# 1-Schematic_EE463_Project.net
KiCad netlist of a schematic drawn in EasyEDA
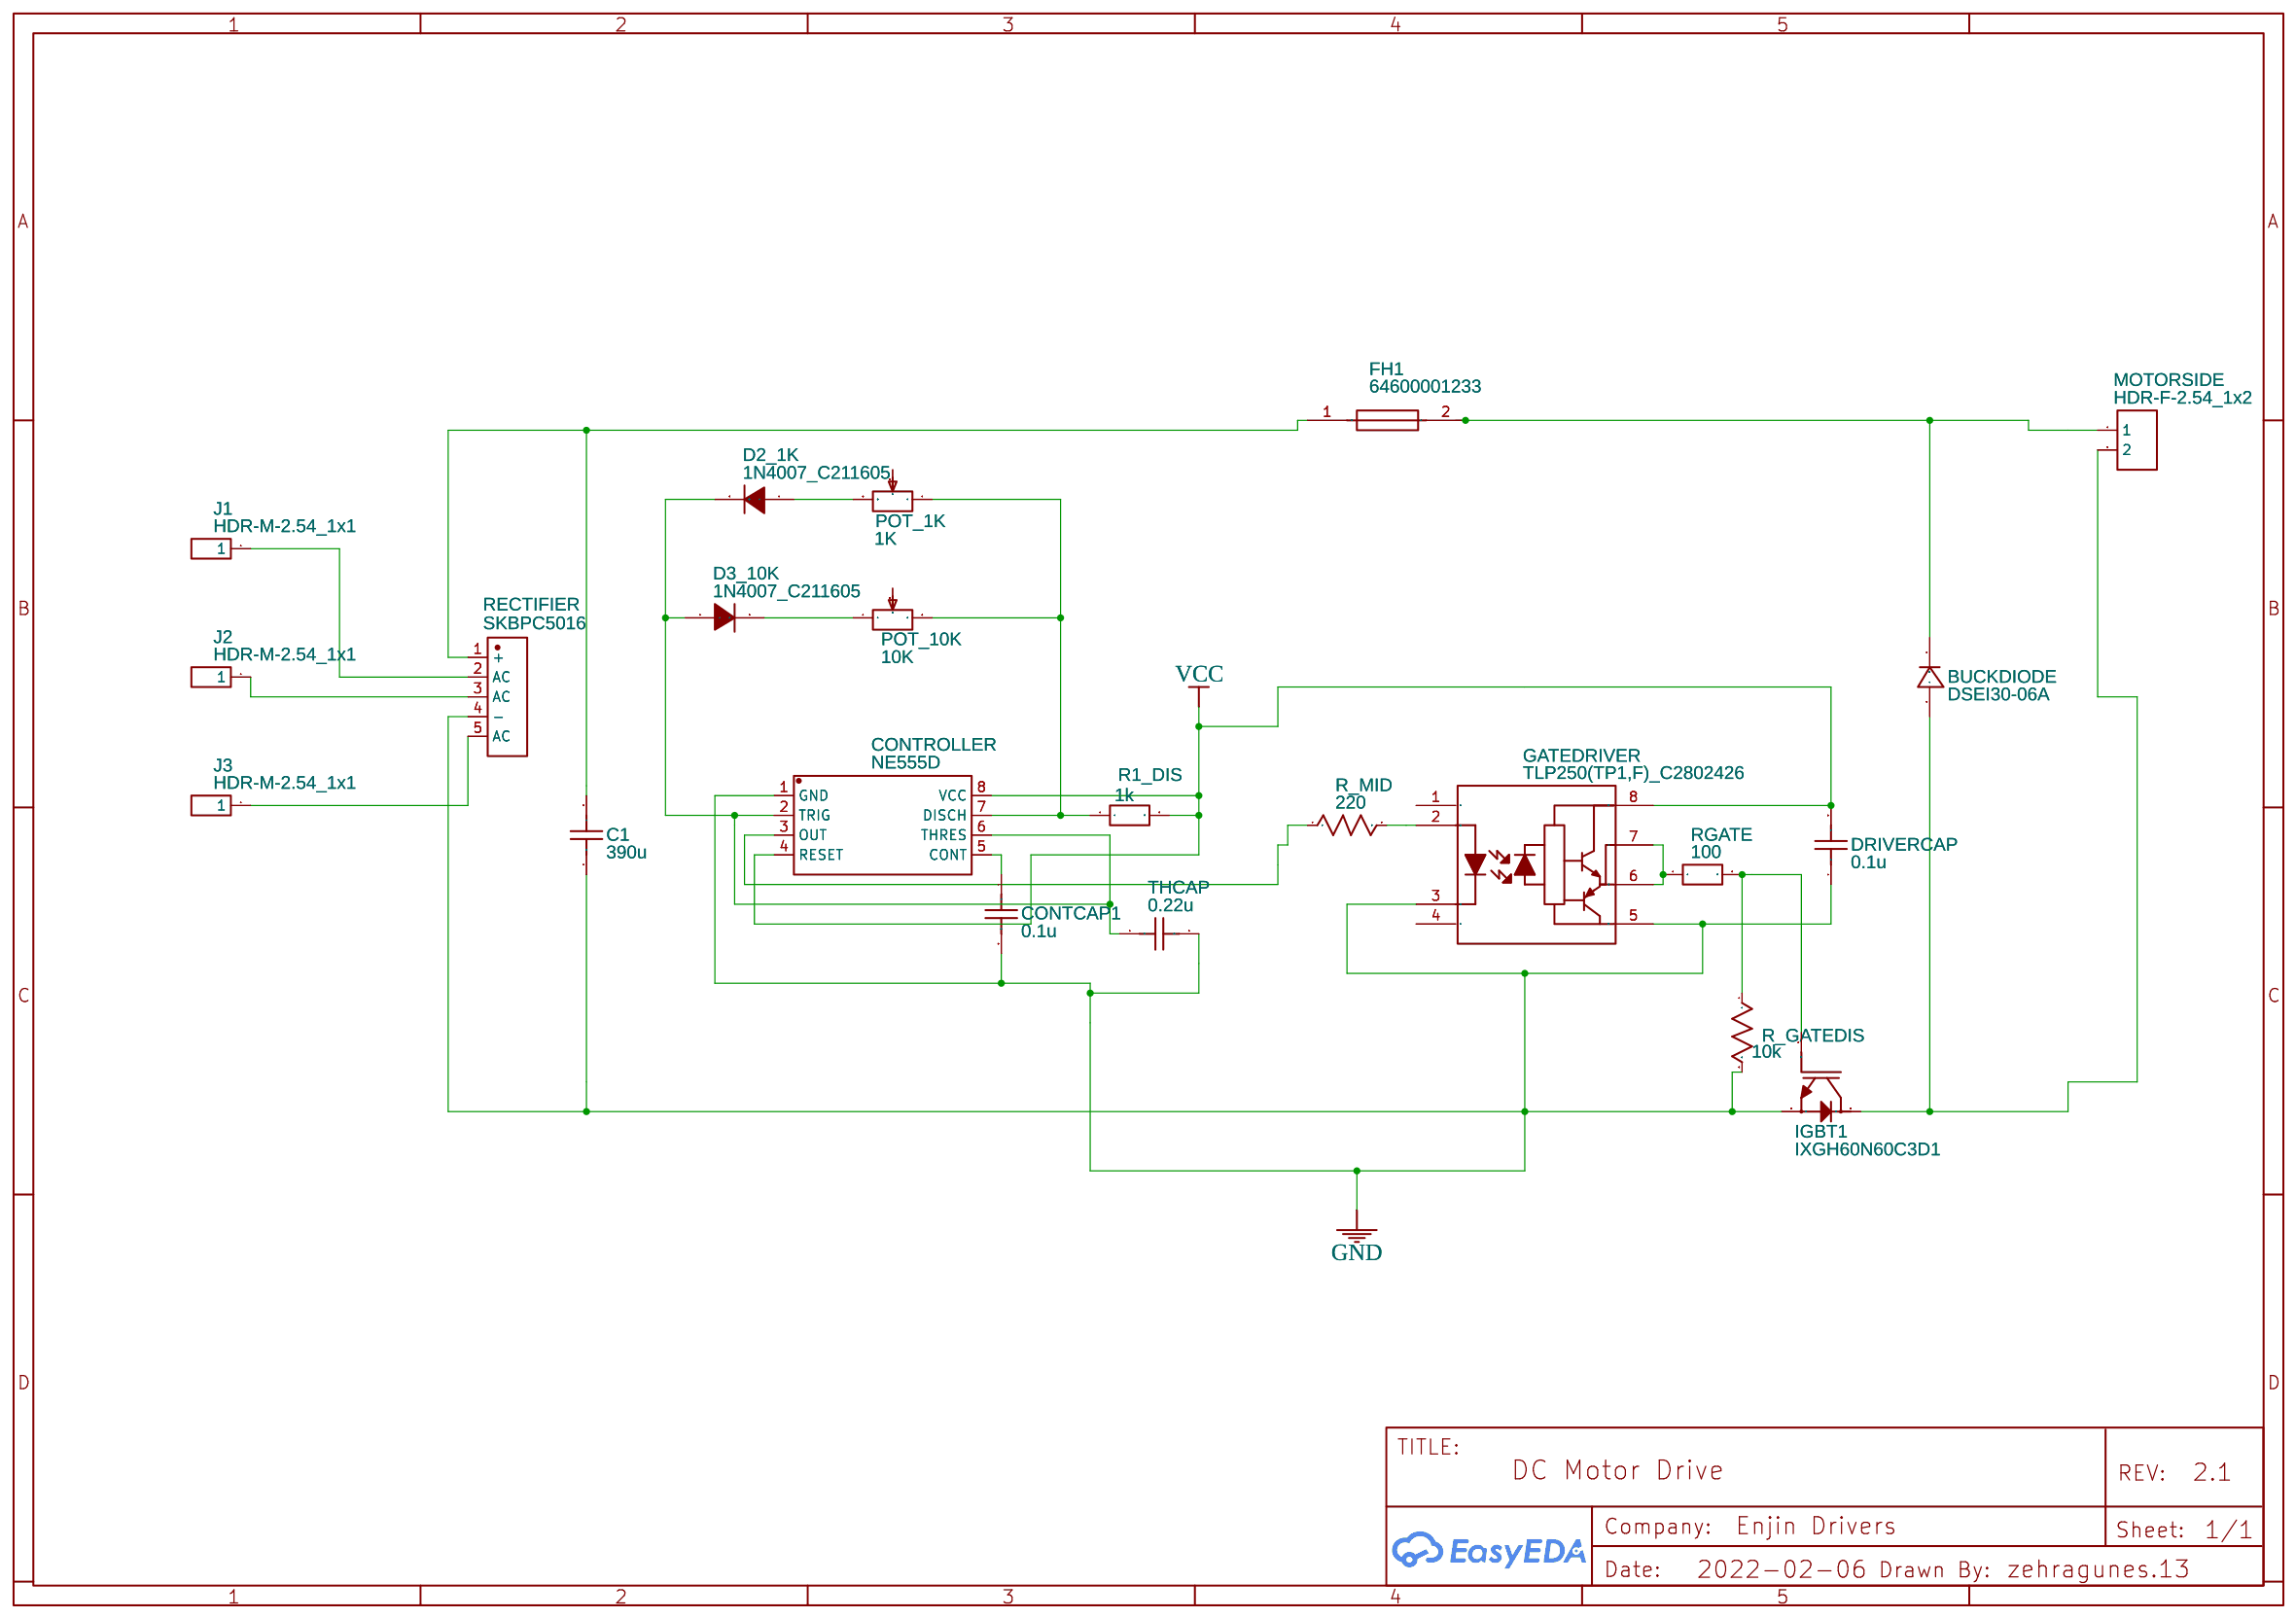
[diagram p0: schematic sheet]

(export (version "E")
  (design (tool "Eeschema 10.0.6"))
  (components
    (comp (ref "BUCKDIODE")
      (value "DSEI30-06A")
      (fields (field (name "BOM_Supplier Part") "C424091"))
      (libsource (lib "") (part "DSEI30-06A"))
    )
    (comp (ref "C1") (value "390u") (libsource (lib "") (part "C_0603_US")))
    (comp (ref "CONTCAP1") (value "0.1u") (libsource (lib "") (part "C_0603_US_3")))
    (comp (ref "CONTROLLER")
      (value "NE555D")
      (fields (field (name "BOM_Supplier Part") "C234230"))
      (libsource (lib "") (part "NE555D"))
    )
    (comp (ref "D2_1K")
      (value "1N4007_C211605")
      (fields (field (name "BOM_Manufacturer Part") "1N4007") (field (name "BOM_Supplier Part") "C211605"))
      (libsource (lib "") (part "1N4007_C211605"))
    )
    (comp (ref "D3_10K")
      (value "1N4007_C211605")
      (fields (field (name "BOM_Manufacturer Part") "1N4007") (field (name "BOM_Supplier Part") "C211605"))
      (libsource (lib "") (part "1N4007_C211605_1"))
    )
    (comp (ref "DRIVERCAP") (value "0.1u") (libsource (lib "") (part "C_0603_US_2")))
    (comp (ref "FH1")
      (value "64600001233")
      (fields (field (name "BOM_Supplier Part") "C2760106"))
      (libsource (lib "") (part "64600001233"))
    )
    (comp (ref "GATEDRIVER")
      (value "TLP250(TP1,F)_C2802426")
      (fields
        (field (name "BOM_Manufacturer Part") "TLP250(TP1,F)")
        (field (name "BOM_Supplier Part") "C2802426")
      )
      (libsource (lib "") (part "TLP250(TP1,F)_C2802426"))
    )
    (comp (ref "IGBT1")
      (value "IXGH60N60C3D1")
      (fields (field (name "BOM_Supplier Part") "C497181"))
      (libsource (lib "") (part "IXGH60N60C3D1"))
    )
    (comp (ref "J1")
      (value "HDR-M-2.54_1x1")
      (fields (field (name "BOM_Supplier Part") "C81276"))
      (libsource (lib "") (part "HDR-M-2.54_1x1"))
    )
    (comp (ref "J2")
      (value "HDR-M-2.54_1x1")
      (fields (field (name "BOM_Supplier Part") "C81276"))
      (libsource (lib "") (part "HDR-M-2.54_1x1"))
    )
    (comp (ref "J3")
      (value "HDR-M-2.54_1x1")
      (fields (field (name "BOM_Supplier Part") "C81276"))
      (libsource (lib "") (part "HDR-M-2.54_1x1"))
    )
    (comp (ref "MOTORSIDE")
      (value "HDR-F-2.54_1x2")
      (fields (field (name "BOM_Supplier Part") "C49661"))
      (libsource (lib "") (part "HDR-F-2.54_1x2"))
    )
    (comp (ref "POT_1K")
      (value "1K")
      (fields
        (field (name "BOM_Manufacturer Part") "EVM3ESX50B13")
        (field (name "BOM_Supplier Part") "C11952")
      )
      (libsource (lib "") (part "EVM3ESX50B13"))
    )
    (comp (ref "POT_10K")
      (value "10K")
      (fields
        (field (name "BOM_Manufacturer Part") "EVM2GSX80B14")
        (field (name "BOM_Supplier Part") "C72381")
      )
      (libsource (lib "") (part "EVM2GSX80B14"))
    )
    (comp (ref "R1_DIS") (value "1k") (libsource (lib "") (part "R_0201_EU")))
    (comp (ref "RECTIFIER")
      (value "SKBPC5016")
      (fields (field (name "BOM_Supplier Part") "C781432"))
      (libsource (lib "") (part "SKBPC5016"))
    )
    (comp (ref "RGATE") (value "100") (libsource (lib "") (part "R_0201_EU_1")))
    (comp (ref "R_GATEDIS") (value "10k") (libsource (lib "") (part "R_0603_US_1")))
    (comp (ref "R_MID") (value "220") (libsource (lib "") (part "R_0603_US")))
    (comp (ref "THCAP") (value "0.22u") (libsource (lib "") (part "C_0603_US_1")))
  )
  (nets
    (net (code "1") (name "GND") (class "Default")
      (node (ref "C1") (pin "1") (pinfunction "1_1") (pintype "unspecified"))
      (node (ref "CONTCAP1") (pin "2") (pinfunction "2_2") (pintype "unspecified"))
      (node (ref "CONTROLLER") (pin "1") (pinfunction "GND_1") (pintype "unspecified"))
      (node (ref "DRIVERCAP") (pin "1") (pinfunction "1_1") (pintype "unspecified"))
      (node (ref "GATEDRIVER") (pin "3") (pinfunction "3_3") (pintype "unspecified"))
      (node (ref "GATEDRIVER") (pin "5") (pinfunction "GND_5") (pintype "passive"))
      (node (ref "IGBT1") (pin "3") (pinfunction "E_3") (pintype "input"))
      (node (ref "RECTIFIER") (pin "4") (pinfunction "-_4") (pintype "unspecified"))
      (node (ref "R_GATEDIS") (pin "2") (pinfunction "2_2") (pintype "unspecified"))
      (node (ref "THCAP") (pin "2") (pinfunction "2_2") (pintype "unspecified"))
    )
    (net (code "2") (name "Net-(BUCKDIODE-A)") (class "Default")
      (node (ref "BUCKDIODE") (pin "3") (pinfunction "A_3") (pintype "unspecified"))
      (node (ref "IGBT1") (pin "2") (pinfunction "C_2") (pintype "input"))
      (node (ref "MOTORSIDE") (pin "2") (pinfunction "2_2") (pintype "input"))
    )
    (net (code "3") (name "Net-(BUCKDIODE-C)") (class "Default")
      (node (ref "BUCKDIODE") (pin "1") (pinfunction "C_1") (pintype "unspecified"))
      (node (ref "FH1") (pin "2") (pinfunction "2_2") (pintype "unspecified"))
      (node (ref "MOTORSIDE") (pin "1") (pinfunction "1_1") (pintype "input"))
    )
    (net (code "4") (name "Net-(CONTROLLER-CONT)") (class "Default")
      (node (ref "CONTCAP1") (pin "1") (pinfunction "1_1") (pintype "unspecified"))
      (node (ref "CONTROLLER") (pin "5") (pinfunction "CONT_5") (pintype "unspecified"))
    )
    (net (code "5") (name "Net-(CONTROLLER-DISCH)") (class "Default")
      (node (ref "CONTROLLER") (pin "7") (pinfunction "DISCH_7") (pintype "unspecified"))
      (node (ref "POT_10K") (pin "3") (pinfunction "3_3") (pintype "input"))
      (node (ref "POT_1K") (pin "1") (pinfunction "1_1") (pintype "input"))
      (node (ref "R1_DIS") (pin "1") (pinfunction "1_1") (pintype "unspecified"))
    )
    (net (code "6") (name "Net-(CONTROLLER-OUT)") (class "Default")
      (node (ref "CONTROLLER") (pin "3") (pinfunction "OUT_3") (pintype "unspecified"))
      (node (ref "R_MID") (pin "1") (pinfunction "1_1") (pintype "unspecified"))
    )
    (net (code "7") (name "Net-(CONTROLLER-THRES)") (class "Default")
      (node (ref "CONTROLLER") (pin "2") (pinfunction "TRIG_2") (pintype "unspecified"))
      (node (ref "CONTROLLER") (pin "6") (pinfunction "THRES_6") (pintype "unspecified"))
      (node (ref "D2_1K") (pin "2") (pinfunction "C_2") (pintype "unspecified"))
      (node (ref "D3_10K") (pin "1") (pinfunction "A_1") (pintype "unspecified"))
      (node (ref "THCAP") (pin "1") (pinfunction "1_1") (pintype "unspecified"))
    )
    (net (code "8") (name "Net-(D2_1K-A)") (class "Default")
      (node (ref "D2_1K") (pin "1") (pinfunction "A_1") (pintype "unspecified"))
      (node (ref "POT_1K") (pin "3") (pinfunction "3_3") (pintype "input"))
    )
    (net (code "9") (name "Net-(D3_10K-C)") (class "Default")
      (node (ref "D3_10K") (pin "2") (pinfunction "C_2") (pintype "unspecified"))
      (node (ref "POT_10K") (pin "1") (pinfunction "1_1") (pintype "input"))
    )
    (net (code "10") (name "Net-(GATEDRIVER-Pad2)") (class "Default")
      (node (ref "GATEDRIVER") (pin "2") (pinfunction "2_2") (pintype "unspecified"))
      (node (ref "R_MID") (pin "2") (pinfunction "2_2") (pintype "unspecified"))
    )
    (net (code "11") (name "Net-(GATEDRIVER-Pad6)") (class "Default")
      (node (ref "GATEDRIVER") (pin "6") (pinfunction "6_6") (pintype "unspecified"))
      (node (ref "GATEDRIVER") (pin "7") (pinfunction "7_7") (pintype "unspecified"))
      (node (ref "RGATE") (pin "1") (pinfunction "1_1") (pintype "unspecified"))
    )
    (net (code "12") (name "Net-(IGBT1-G)") (class "Default")
      (node (ref "IGBT1") (pin "1") (pinfunction "G_1") (pintype "input"))
      (node (ref "RGATE") (pin "2") (pinfunction "2_2") (pintype "unspecified"))
      (node (ref "R_GATEDIS") (pin "1") (pinfunction "1_1") (pintype "unspecified"))
    )
    (net (code "13") (name "Net-(J1-Pad1)") (class "Default")
      (node (ref "J1") (pin "1") (pinfunction "1_1") (pintype "input"))
      (node (ref "RECTIFIER") (pin "2") (pinfunction "AC_2") (pintype "unspecified"))
    )
    (net (code "14") (name "Net-(J2-Pad1)") (class "Default")
      (node (ref "J2") (pin "1") (pinfunction "1_1") (pintype "input"))
      (node (ref "RECTIFIER") (pin "3") (pinfunction "AC_3") (pintype "unspecified"))
    )
    (net (code "15") (name "Net-(J3-Pad1)") (class "Default")
      (node (ref "J3") (pin "1") (pinfunction "1_1") (pintype "input"))
      (node (ref "RECTIFIER") (pin "5") (pinfunction "AC_5") (pintype "unspecified"))
    )
    (net (code "16") (name "Net-(RECTIFIER-+)") (class "Default")
      (node (ref "C1") (pin "2") (pinfunction "2_2") (pintype "unspecified"))
      (node (ref "FH1") (pin "1") (pinfunction "1_1") (pintype "unspecified"))
      (node (ref "RECTIFIER") (pin "1") (pinfunction "+_1") (pintype "unspecified"))
    )
    (net (code "17") (name "VCC") (class "Default")
      (node (ref "CONTROLLER") (pin "4") (pinfunction "RESET_4") (pintype "unspecified"))
      (node (ref "CONTROLLER") (pin "8") (pinfunction "VCC_8") (pintype "unspecified"))
      (node (ref "DRIVERCAP") (pin "2") (pinfunction "2_2") (pintype "unspecified"))
      (node (ref "GATEDRIVER") (pin "8") (pinfunction "VCC_8") (pintype "passive"))
      (node (ref "R1_DIS") (pin "2") (pinfunction "2_2") (pintype "unspecified"))
    )
    (net (code "18") (name "unconnected-(GATEDRIVER-Pad1)") (class "Default")
      (node (ref "GATEDRIVER") (pin "1") (pinfunction "1_1") (pintype "unspecified"))
    )
    (net (code "19") (name "unconnected-(GATEDRIVER-Pad4)") (class "Default")
      (node (ref "GATEDRIVER") (pin "4") (pinfunction "4_4") (pintype "unspecified"))
    )
    (net (code "20") (name "unconnected-(POT_1K-Pad2)") (class "Default")
      (node (ref "POT_1K") (pin "2") (pinfunction "2_2") (pintype "input"))
    )
    (net (code "21") (name "unconnected-(POT_10K-Pad2)") (class "Default")
      (node (ref "POT_10K") (pin "2") (pinfunction "2_2") (pintype "input"))
    )
  )
)
